# DMTV_SD.net
KiCad netlist of a schematic drawn in EAGLE
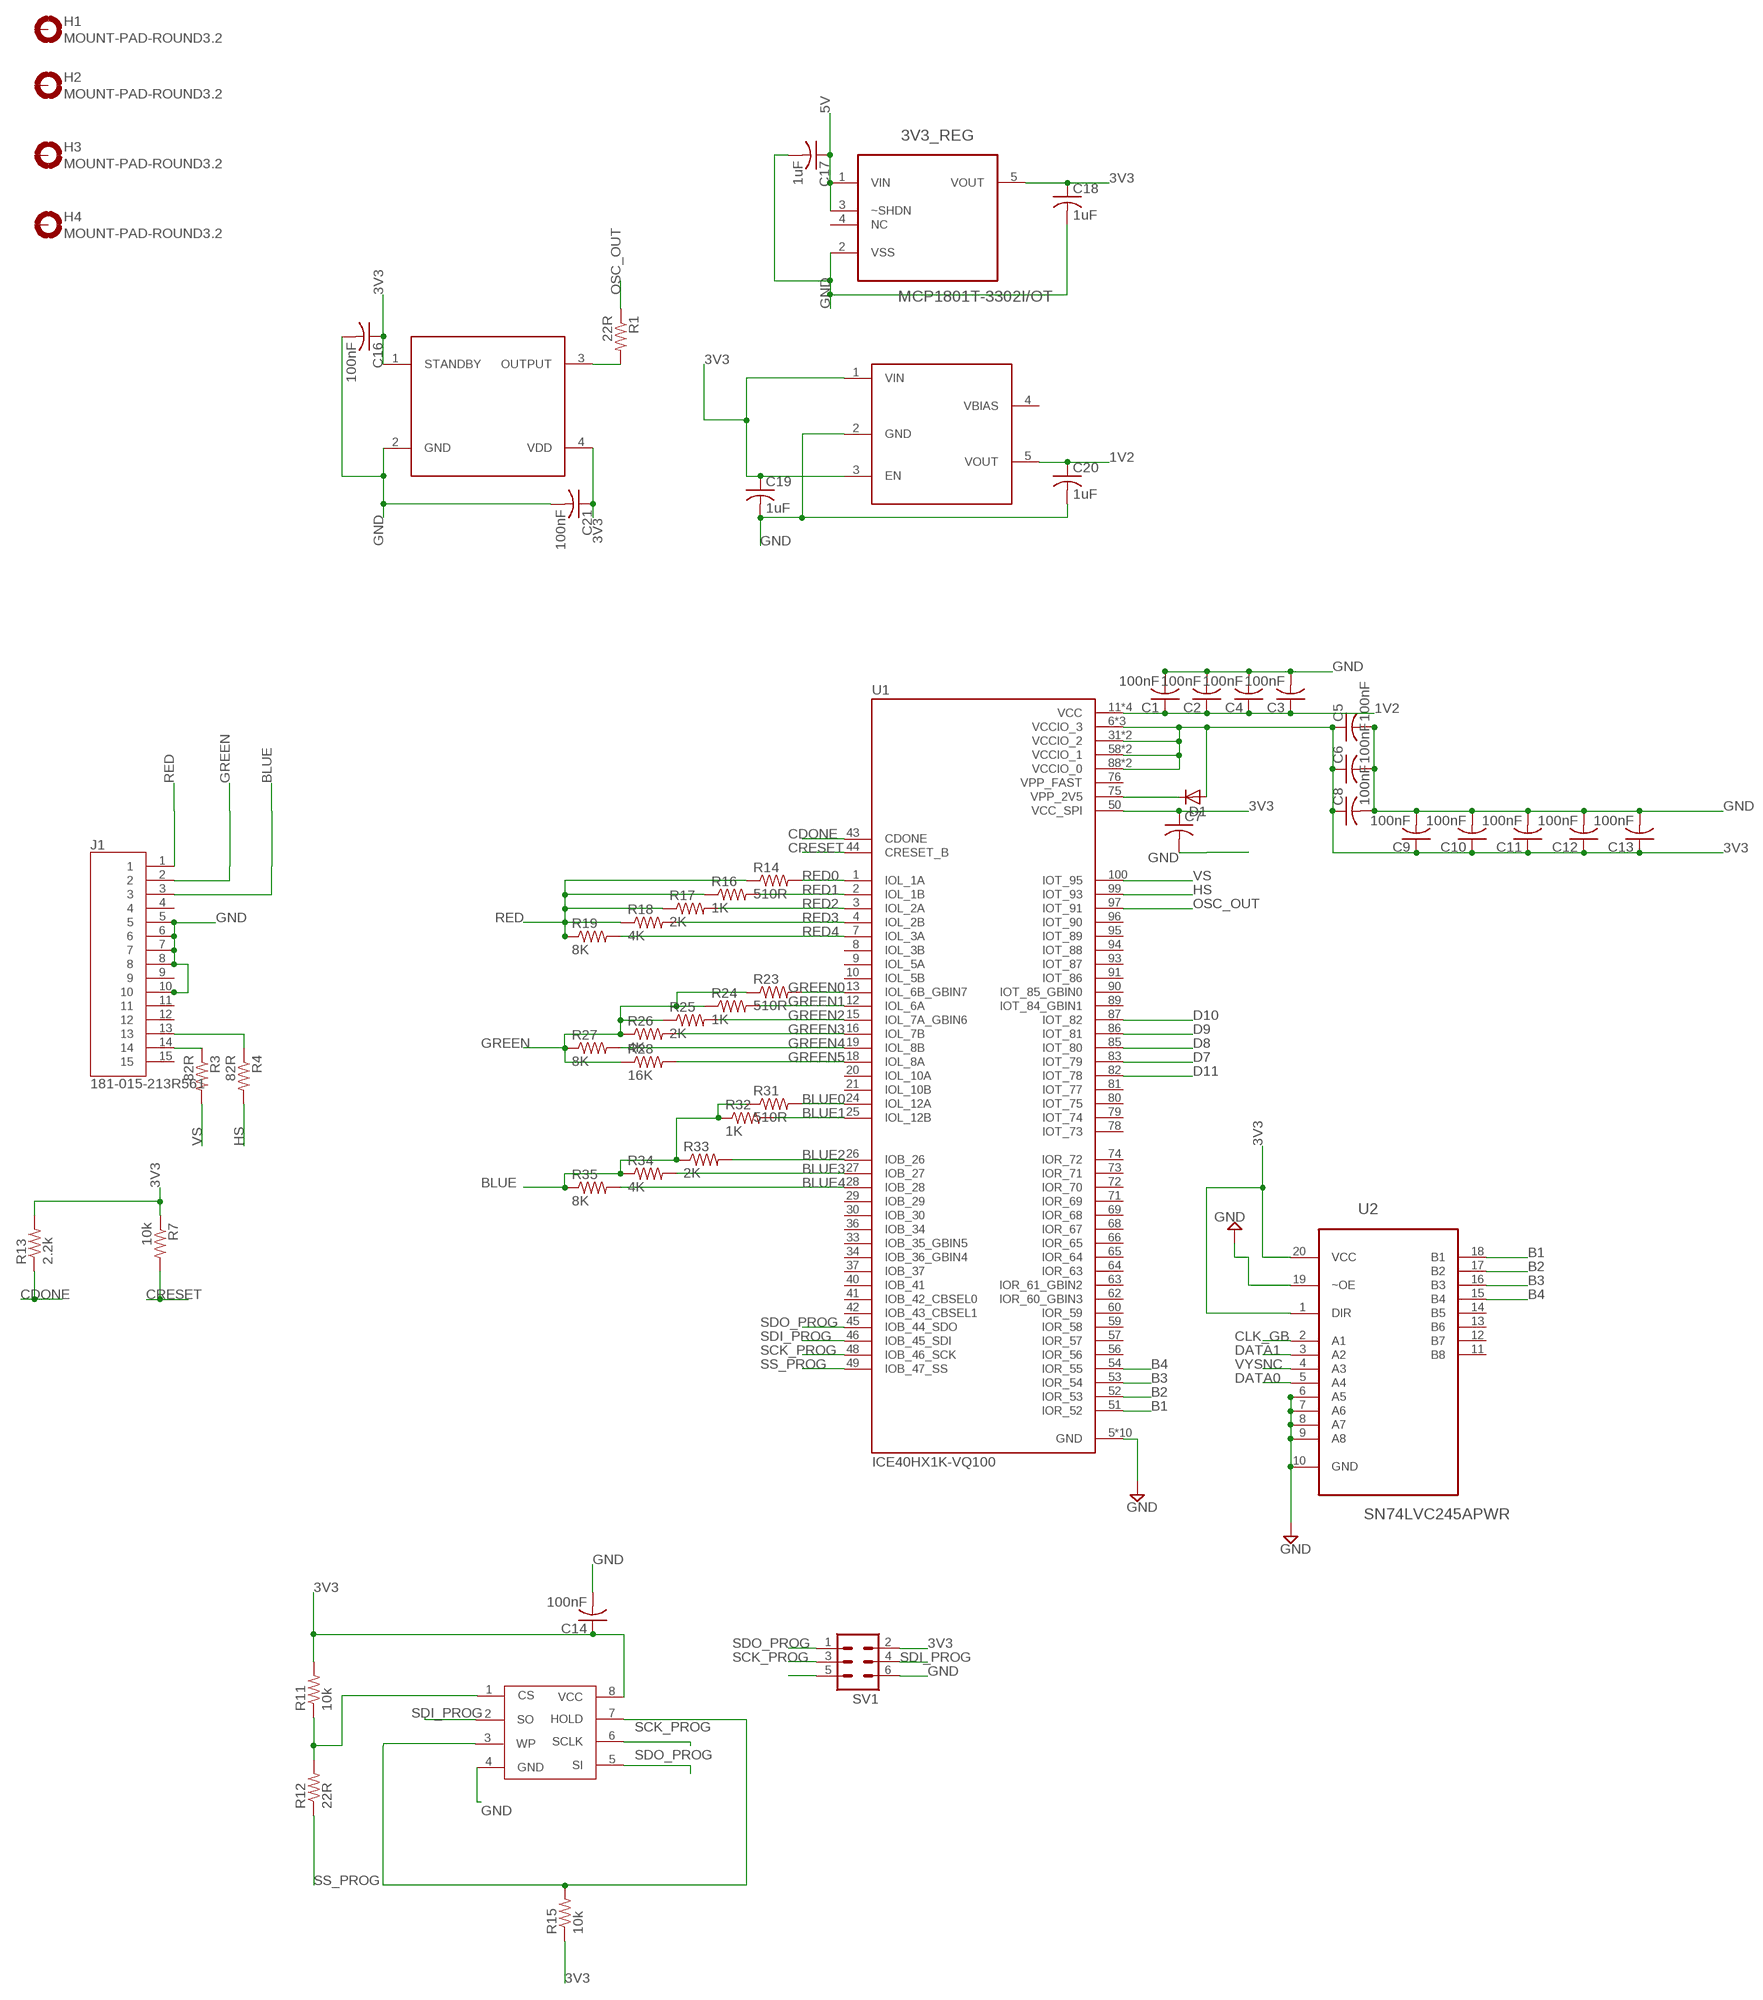
[diagram p0: schematic, sheet 1]
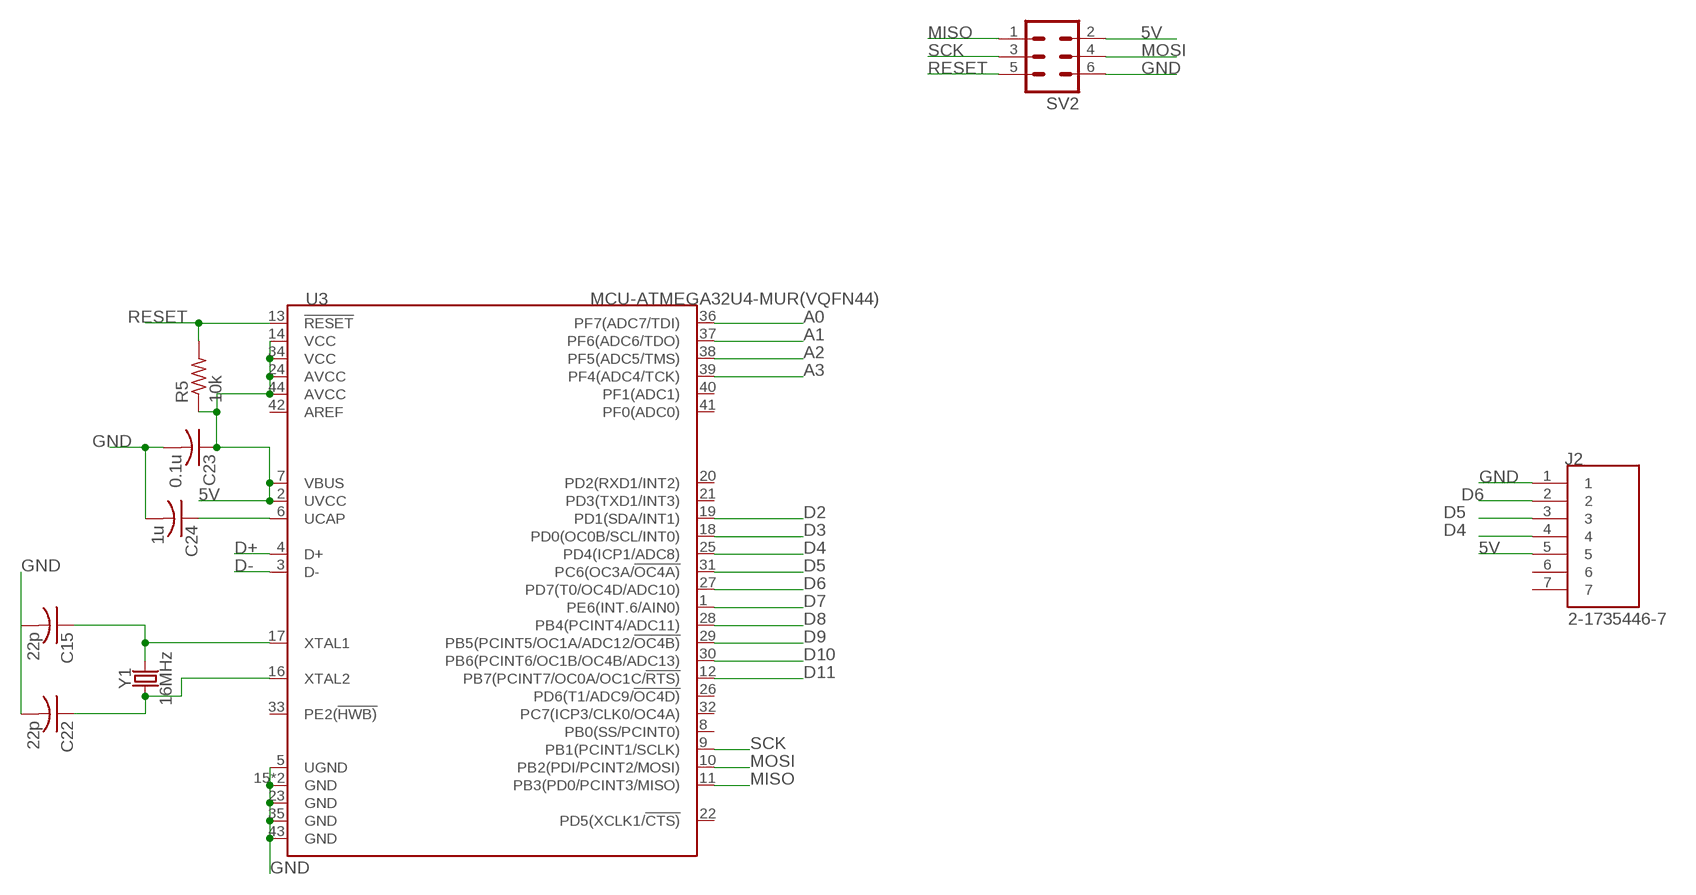
[diagram p1: schematic, sheet 2]
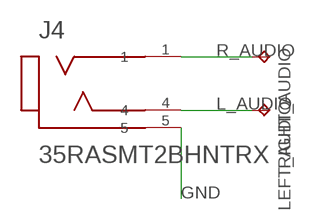
[diagram p2: schematic, sheet 3]
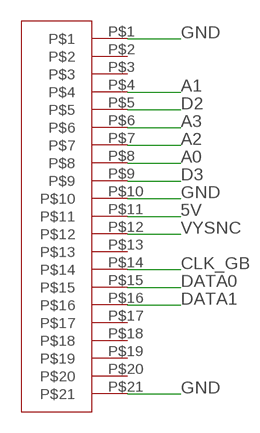
[diagram p3: schematic, sheet 4]

(export (version "E")
  (design (tool "Eeschema 10.0.6"))
  (components
    (comp (ref "C15")
      (value "22p")
      (footprint "eagle-import:C0805")
      (libsource (lib "eagle-import") (part "C-USC0805"))
    )
    (comp (ref "C22")
      (value "22p")
      (footprint "eagle-import:C0805")
      (libsource (lib "eagle-import") (part "C-USC0805"))
    )
    (comp (ref "C23")
      (value "0.1u")
      (footprint "eagle-import:C0805")
      (libsource (lib "eagle-import") (part "C-USC0805"))
    )
    (comp (ref "C24")
      (value "1u")
      (footprint "eagle-import:C0805")
      (libsource (lib "eagle-import") (part "C-USC0805"))
    )
    (comp (ref "J2")
      (value "2-1735446-7")
      (footprint "eagle-import:TE_2-1735446-7")
      (fields (field (name "MF") "TE Connectivity"))
      (libsource (lib "eagle-import") (part "2-1735446-7"))
    )
    (comp (ref "R5")
      (value "10k")
      (footprint "eagle-import:R0805")
      (libsource (lib "eagle-import") (part "R-US_R0805"))
    )
    (comp (ref "SV2")
      (value "MA03-2")
      (footprint "eagle-import:MA03-2")
      (libsource (lib "eagle-import") (part "MA03-2"))
    )
    (comp (ref "U3")
      (value "MCU-ATMEGA32U4-MUR(VQFN44)")
      (footprint "eagle-import:QFN44G-0.5-7X7MM")
      (fields (field (name "MF") "Microchip") (field (name "MP") "ATMEGA32U4-MUR"))
      (libsource (lib "eagle-import") (part "MCU-ATMEGA32U4-MUR(VQFN44)"))
    )
    (comp (ref "Y1")
      (value "16MHz")
      (footprint "eagle-import:CRYSTAL-SMD-5X3.2-4PAD")
      (libsource (lib "eagle-import") (part "CRYSTAL-16MHZSMD-5X3.2"))
    )
    (comp (ref "U$6")
      (value "52808-21700520452145")
      (footprint "eagle-import:0520452145")
      (libsource (lib "eagle-import") (part "52808-21700520452145"))
    )
    (comp (ref "3V3_REG")
      (value "MCP1801T-3302I/OT")
      (footprint "eagle-import:SOT95P270X145-5N")
      (fields (field (name "DIGI-KEY_PART_NUMBER") "MCP1801T-3302I/OTCT-ND") (field (name "MF") "Microchip"))
      (libsource (lib "eagle-import") (part "MCP1801T-3302I/OT"))
    )
    (comp (ref "C1")
      (value "100nF")
      (footprint "eagle-import:C0603")
      (libsource (lib "eagle-import") (part "C-USC0603"))
    )
    (comp (ref "C2")
      (value "100nF")
      (footprint "eagle-import:C0603")
      (libsource (lib "eagle-import") (part "C-USC0603"))
    )
    (comp (ref "C3")
      (value "100nF")
      (footprint "eagle-import:C0603")
      (libsource (lib "eagle-import") (part "C-USC0603"))
    )
    (comp (ref "C4")
      (value "100nF")
      (footprint "eagle-import:C0603")
      (libsource (lib "eagle-import") (part "C-USC0603"))
    )
    (comp (ref "C5")
      (value "100nF")
      (footprint "eagle-import:C0603")
      (libsource (lib "eagle-import") (part "C-USC0603"))
    )
    (comp (ref "C6")
      (value "100nF")
      (footprint "eagle-import:C0603")
      (libsource (lib "eagle-import") (part "C-USC0603"))
    )
    (comp (ref "C7")
      (value "C-USC0603")
      (footprint "eagle-import:C0603")
      (libsource (lib "eagle-import") (part "C-USC0603"))
    )
    (comp (ref "C8")
      (value "100nF")
      (footprint "eagle-import:C0603")
      (libsource (lib "eagle-import") (part "C-USC0603"))
    )
    (comp (ref "C9")
      (value "100nF")
      (footprint "eagle-import:C0603")
      (libsource (lib "eagle-import") (part "C-USC0603"))
    )
    (comp (ref "C10")
      (value "100nF")
      (footprint "eagle-import:C0603")
      (libsource (lib "eagle-import") (part "C-USC0603"))
    )
    (comp (ref "C11")
      (value "100nF")
      (footprint "eagle-import:C0603")
      (libsource (lib "eagle-import") (part "C-USC0603"))
    )
    (comp (ref "C12")
      (value "100nF")
      (footprint "eagle-import:C0603")
      (libsource (lib "eagle-import") (part "C-USC0603"))
    )
    (comp (ref "C13")
      (value "100nF")
      (footprint "eagle-import:C0603")
      (libsource (lib "eagle-import") (part "C-USC0603"))
    )
    (comp (ref "C14")
      (value "100nF")
      (footprint "eagle-import:C0603")
      (libsource (lib "eagle-import") (part "C-USC0603"))
    )
    (comp (ref "C16")
      (value "100nF")
      (footprint "eagle-import:C0603")
      (libsource (lib "eagle-import") (part "C-USC0603"))
    )
    (comp (ref "C17")
      (value "1uF")
      (footprint "eagle-import:C0805")
      (libsource (lib "eagle-import") (part "C-USC0805"))
    )
    (comp (ref "C18")
      (value "1uF")
      (footprint "eagle-import:C0805")
      (libsource (lib "eagle-import") (part "C-USC0805"))
    )
    (comp (ref "C19")
      (value "1uF")
      (footprint "eagle-import:C0805")
      (libsource (lib "eagle-import") (part "C-USC0805"))
    )
    (comp (ref "C20")
      (value "1uF")
      (footprint "eagle-import:C0805")
      (libsource (lib "eagle-import") (part "C-USC0805"))
    )
    (comp (ref "C21")
      (value "100nF")
      (footprint "eagle-import:C0603")
      (libsource (lib "eagle-import") (part "C-USC0603"))
    )
    (comp (ref "D1")
      (value "D-SOD123")
      (footprint "eagle-import:SOD123")
      (libsource (lib "eagle-import") (part "D-SOD123"))
    )
    (comp (ref "H1")
      (value "MOUNT-PAD-ROUND3.2")
      (footprint "eagle-import:3,2-PAD")
      (libsource (lib "eagle-import") (part "MOUNT-PAD-ROUND3.2"))
    )
    (comp (ref "H2")
      (value "MOUNT-PAD-ROUND3.2")
      (footprint "eagle-import:3,2-PAD")
      (libsource (lib "eagle-import") (part "MOUNT-PAD-ROUND3.2"))
    )
    (comp (ref "H3")
      (value "MOUNT-PAD-ROUND3.2")
      (footprint "eagle-import:3,2-PAD")
      (libsource (lib "eagle-import") (part "MOUNT-PAD-ROUND3.2"))
    )
    (comp (ref "H4")
      (value "MOUNT-PAD-ROUND3.2")
      (footprint "eagle-import:3,2-PAD")
      (libsource (lib "eagle-import") (part "MOUNT-PAD-ROUND3.2"))
    )
    (comp (ref "J1")
      (value "181-015-213R561")
      (footprint "eagle-import:NORCOMP_181-015-213R561")
      (fields (field (name "MF") "NorComp Inc."))
      (libsource (lib "eagle-import") (part "181-015-213R561"))
    )
    (comp (ref "R1")
      (value "22R")
      (footprint "eagle-import:R0603")
      (libsource (lib "eagle-import") (part "resistor_348_R-US_R0603"))
    )
    (comp (ref "R3")
      (value "82R")
      (footprint "eagle-import:R0603")
      (libsource (lib "eagle-import") (part "resistor_348_R-US_R0603"))
    )
    (comp (ref "R4")
      (value "82R")
      (footprint "eagle-import:R0603")
      (libsource (lib "eagle-import") (part "resistor_348_R-US_R0603"))
    )
    (comp (ref "R7")
      (value "10k")
      (footprint "eagle-import:R0603")
      (libsource (lib "eagle-import") (part "resistor_348_R-US_R0603"))
    )
    (comp (ref "R11")
      (value "10k")
      (footprint "eagle-import:R0603")
      (libsource (lib "eagle-import") (part "R-US_R0603"))
    )
    (comp (ref "R12")
      (value "22R")
      (footprint "eagle-import:R0603")
      (libsource (lib "eagle-import") (part "R-US_R0603"))
    )
    (comp (ref "R13")
      (value "2.2k")
      (footprint "eagle-import:R0603")
      (libsource (lib "eagle-import") (part "R-US_R0603"))
    )
    (comp (ref "R14")
      (value "510R")
      (footprint "eagle-import:R0603")
      (libsource (lib "eagle-import") (part "resistor_348_R-US_R0603"))
    )
    (comp (ref "R15")
      (value "10k")
      (footprint "eagle-import:R0603")
      (libsource (lib "eagle-import") (part "R-US_R0603"))
    )
    (comp (ref "R16")
      (value "1K")
      (footprint "eagle-import:R0603")
      (libsource (lib "eagle-import") (part "resistor_348_R-US_R0603"))
    )
    (comp (ref "R17")
      (value "2K")
      (footprint "eagle-import:R0603")
      (libsource (lib "eagle-import") (part "resistor_348_R-US_R0603"))
    )
    (comp (ref "R18")
      (value "4K")
      (footprint "eagle-import:R0603")
      (libsource (lib "eagle-import") (part "resistor_348_R-US_R0603"))
    )
    (comp (ref "R19")
      (value "8K")
      (footprint "eagle-import:R0603")
      (libsource (lib "eagle-import") (part "resistor_348_R-US_R0603"))
    )
    (comp (ref "R23")
      (value "510R")
      (footprint "eagle-import:R0603")
      (libsource (lib "eagle-import") (part "resistor_348_R-US_R0603"))
    )
    (comp (ref "R24")
      (value "1K")
      (footprint "eagle-import:R0603")
      (libsource (lib "eagle-import") (part "resistor_348_R-US_R0603"))
    )
    (comp (ref "R25")
      (value "2K")
      (footprint "eagle-import:R0603")
      (libsource (lib "eagle-import") (part "resistor_348_R-US_R0603"))
    )
    (comp (ref "R26")
      (value "4K")
      (footprint "eagle-import:R0603")
      (libsource (lib "eagle-import") (part "resistor_348_R-US_R0603"))
    )
    (comp (ref "R27")
      (value "8K")
      (footprint "eagle-import:R0603")
      (libsource (lib "eagle-import") (part "resistor_348_R-US_R0603"))
    )
    (comp (ref "R28")
      (value "16K")
      (footprint "eagle-import:R0603")
      (libsource (lib "eagle-import") (part "resistor_348_R-US_R0603"))
    )
    (comp (ref "R31")
      (value "510R")
      (footprint "eagle-import:R0603")
      (libsource (lib "eagle-import") (part "resistor_348_R-US_R0603"))
    )
    (comp (ref "R32")
      (value "1K")
      (footprint "eagle-import:R0603")
      (libsource (lib "eagle-import") (part "resistor_348_R-US_R0603"))
    )
    (comp (ref "R33")
      (value "2K")
      (footprint "eagle-import:R0603")
      (libsource (lib "eagle-import") (part "resistor_348_R-US_R0603"))
    )
    (comp (ref "R34")
      (value "4K")
      (footprint "eagle-import:R0603")
      (libsource (lib "eagle-import") (part "resistor_348_R-US_R0603"))
    )
    (comp (ref "R35")
      (value "8K")
      (footprint "eagle-import:R0603")
      (libsource (lib "eagle-import") (part "resistor_348_R-US_R0603"))
    )
    (comp (ref "SV1")
      (value "MA03-2")
      (footprint "eagle-import:MA03-2")
      (libsource (lib "eagle-import") (part "MA03-2"))
    )
    (comp (ref "U$1")
      (value "SIT8008BI-13-18E-25.175000G")
      (footprint "eagle-import:XTAL_ASDM1-25.000MHZ-LC-T")
      (libsource (lib "eagle-import") (part "XTAL_ASDM1-25.000MHZ-LC-T"))
    )
    (comp (ref "U$2")
      (value "TLV70012DDCR")
      (footprint "eagle-import:SOT95P280X100-5N")
      (libsource (lib "eagle-import") (part "SOT95P280X100-5N"))
    )
    (comp (ref "U$5")
      (value "MX25L1006EMI-10G")
      (footprint "eagle-import:SOIC-8")
      (libsource (lib "eagle-import") (part "MX25L1006EMI-10G"))
    )
    (comp (ref "U1")
      (value "ICE40HX1K-VQ100")
      (footprint "eagle-import:QFP50P1600X1600X120-100N")
      (fields (field (name "DIGI-KEY_PART_NUMBER") "220-1567-ND") (field (name "MF") "Lattice Semiconductor"))
      (libsource (lib "eagle-import") (part "ICE40HX1K-VQ100"))
    )
    (comp (ref "U2")
      (value "SN74LVC245APWR")
      (footprint "eagle-import:SOP65P640X120-20N")
      (fields (field (name "DIGI-KEY_PART_NUMBER") "296-1233-1-ND") (field (name "MF") "Texas Instruments"))
      (libsource (lib "eagle-import") (part "SN74LVC245APWR"))
    )
    (comp (ref "J4")
      (value "35RASMT2BHNTRX")
      (footprint "eagle-import:SWITCHCRAFT_35RASMT2BHNTRX")
      (fields (field (name "MF") "Switchcraft"))
      (libsource (lib "eagle-import") (part "35RASMT2BHNTRX"))
    )
    (comp (ref "LEFT_AUDIO")
      (value "TPB2,54")
      (footprint "eagle-import:B2,54")
      (libsource (lib "eagle-import") (part "TPB2,54"))
    )
    (comp (ref "RIGHT_AUDIO")
      (value "TPB2,54")
      (footprint "eagle-import:B2,54")
      (libsource (lib "eagle-import") (part "TPB2,54"))
    )
  )
  (nets
    (net (code "1") (name "1V2") (class "Default")
      (node (ref "C1") (pin "1") (pinfunction "1_1") (pintype "passive"))
      (node (ref "C2") (pin "1") (pinfunction "1_1") (pintype "passive"))
      (node (ref "C20") (pin "1") (pinfunction "1_1") (pintype "passive"))
      (node (ref "C3") (pin "1") (pinfunction "1_1") (pintype "passive"))
      (node (ref "C4") (pin "1") (pinfunction "1_1") (pintype "passive"))
      (node (ref "U$2") (pin "5") (pinfunction "VOUT_5") (pintype "bidirectional"))
      (node (ref "U1") (pin "11") (pinfunction "VCC_11") (pintype "power_in"))
      (node (ref "U1") (pin "35") (pinfunction "VCC_35") (pintype "power_in"))
      (node (ref "U1") (pin "61") (pinfunction "VCC_61") (pintype "power_in"))
      (node (ref "U1") (pin "77") (pinfunction "VCC_77") (pintype "power_in"))
    )
    (net (code "2") (name "3V3") (class "Default")
      (node (ref "3V3_REG") (pin "5") (pinfunction "VOUT_5") (pintype "output"))
      (node (ref "C10") (pin "1") (pinfunction "1_1") (pintype "passive"))
      (node (ref "C11") (pin "1") (pinfunction "1_1") (pintype "passive"))
      (node (ref "C12") (pin "1") (pinfunction "1_1") (pintype "passive"))
      (node (ref "C13") (pin "1") (pinfunction "1_1") (pintype "passive"))
      (node (ref "C14") (pin "1") (pinfunction "1_1") (pintype "passive"))
      (node (ref "C16") (pin "1") (pinfunction "1_1") (pintype "passive"))
      (node (ref "C18") (pin "1") (pinfunction "1_1") (pintype "passive"))
      (node (ref "C19") (pin "1") (pinfunction "1_1") (pintype "passive"))
      (node (ref "C21") (pin "1") (pinfunction "1_1") (pintype "passive"))
      (node (ref "C5") (pin "1") (pinfunction "1_1") (pintype "passive"))
      (node (ref "C6") (pin "1") (pinfunction "1_1") (pintype "passive"))
      (node (ref "C7") (pin "1") (pinfunction "1_1") (pintype "passive"))
      (node (ref "C8") (pin "1") (pinfunction "1_1") (pintype "passive"))
      (node (ref "C9") (pin "1") (pinfunction "1_1") (pintype "passive"))
      (node (ref "D1") (pin "2") (pinfunction "A_2") (pintype "passive"))
      (node (ref "R11") (pin "2") (pinfunction "2_2") (pintype "passive"))
      (node (ref "R13") (pin "2") (pinfunction "2_2") (pintype "passive"))
      (node (ref "R15") (pin "1") (pinfunction "1_1") (pintype "passive"))
      (node (ref "R7") (pin "1") (pinfunction "1_1") (pintype "passive"))
      (node (ref "SV1") (pin "2") (pinfunction "2_2") (pintype "passive"))
      (node (ref "U$1") (pin "1") (pinfunction "STANDBY_1") (pintype "bidirectional"))
      (node (ref "U$1") (pin "4") (pinfunction "VDD_4") (pintype "bidirectional"))
      (node (ref "U$2") (pin "1") (pinfunction "VIN_1") (pintype "bidirectional"))
      (node (ref "U$2") (pin "3") (pinfunction "EN_3") (pintype "bidirectional"))
      (node (ref "U$5") (pin "8") (pinfunction "VCC_8") (pintype "bidirectional"))
      (node (ref "U1") (pin "14") (pinfunction "VCCIO_3_14") (pintype "power_in"))
      (node (ref "U1") (pin "22") (pinfunction "VCCIO_3_22") (pintype "power_in"))
      (node (ref "U1") (pin "31") (pinfunction "VCCIO_2_31") (pintype "power_in"))
      (node (ref "U1") (pin "38") (pinfunction "VCCIO_2_38") (pintype "power_in"))
      (node (ref "U1") (pin "50") (pinfunction "VCC_SPI_50") (pintype "power_in"))
      (node (ref "U1") (pin "58") (pinfunction "VCCIO_1_58") (pintype "power_in"))
      (node (ref "U1") (pin "6") (pinfunction "VCCIO_3_6") (pintype "power_in"))
      (node (ref "U1") (pin "67") (pinfunction "VCCIO_1_67") (pintype "power_in"))
      (node (ref "U1") (pin "88") (pinfunction "VCCIO_0_88") (pintype "power_in"))
      (node (ref "U1") (pin "92") (pinfunction "VCCIO_0_92") (pintype "power_in"))
      (node (ref "U2") (pin "1") (pinfunction "DIR_1") (pintype "input"))
      (node (ref "U2") (pin "20") (pinfunction "VCC_20") (pintype "power_in"))
    )
    (net (code "3") (name "5V") (class "Default")
      (node (ref "3V3_REG") (pin "1") (pinfunction "VIN_1") (pintype "power_in"))
      (node (ref "3V3_REG") (pin "3") (pinfunction "~{SHDN}_3") (pintype "input"))
      (node (ref "C17") (pin "1") (pinfunction "1_1") (pintype "passive"))
      (node (ref "C23") (pin "1") (pinfunction "1_1") (pintype "passive"))
      (node (ref "J2") (pin "5") (pinfunction "5_5") (pintype "passive"))
      (node (ref "R5") (pin "1") (pinfunction "1_1") (pintype "passive"))
      (node (ref "SV2") (pin "2") (pinfunction "2_2") (pintype "passive"))
      (node (ref "U$6") (pin "P$11") (pinfunction "P$11_P$11") (pintype "bidirectional"))
      (node (ref "U3") (pin "14") (pinfunction "VCC_14") (pintype "bidirectional"))
      (node (ref "U3") (pin "2") (pinfunction "UVCC_2") (pintype "bidirectional"))
      (node (ref "U3") (pin "24") (pinfunction "AVCC_24") (pintype "bidirectional"))
      (node (ref "U3") (pin "34") (pinfunction "VCC_34") (pintype "bidirectional"))
      (node (ref "U3") (pin "44") (pinfunction "AVCC_44") (pintype "bidirectional"))
      (node (ref "U3") (pin "7") (pinfunction "VBUS_7") (pintype "bidirectional"))
    )
    (net (code "4") (name "A0") (class "Default")
      (node (ref "U$6") (pin "P$8") (pinfunction "P$8_P$8") (pintype "bidirectional"))
      (node (ref "U3") (pin "36") (pinfunction "PF7(ADC7/TDI)_36") (pintype "bidirectional"))
    )
    (net (code "5") (name "A1") (class "Default")
      (node (ref "U$6") (pin "P$4") (pinfunction "P$4_P$4") (pintype "bidirectional"))
      (node (ref "U3") (pin "37") (pinfunction "PF6(ADC6/TDO)_37") (pintype "bidirectional"))
    )
    (net (code "6") (name "A2") (class "Default")
      (node (ref "U$6") (pin "P$7") (pinfunction "P$7_P$7") (pintype "bidirectional"))
      (node (ref "U3") (pin "38") (pinfunction "PF5(ADC5/TMS)_38") (pintype "bidirectional"))
    )
    (net (code "7") (name "A3") (class "Default")
      (node (ref "U$6") (pin "P$6") (pinfunction "P$6_P$6") (pintype "bidirectional"))
      (node (ref "U3") (pin "39") (pinfunction "PF4(ADC4/TCK)_39") (pintype "bidirectional"))
    )
    (net (code "8") (name "B1") (class "Default")
      (node (ref "U1") (pin "51") (pinfunction "IOR_52_51") (pintype "bidirectional"))
      (node (ref "U2") (pin "18") (pinfunction "B1_18") (pintype "bidirectional"))
    )
    (net (code "9") (name "B2") (class "Default")
      (node (ref "U1") (pin "52") (pinfunction "IOR_53_52") (pintype "bidirectional"))
      (node (ref "U2") (pin "17") (pinfunction "B2_17") (pintype "bidirectional"))
    )
    (net (code "10") (name "B3") (class "Default")
      (node (ref "U1") (pin "53") (pinfunction "IOR_54_53") (pintype "bidirectional"))
      (node (ref "U2") (pin "16") (pinfunction "B3_16") (pintype "bidirectional"))
    )
    (net (code "11") (name "B4") (class "Default")
      (node (ref "U1") (pin "54") (pinfunction "IOR_55_54") (pintype "bidirectional"))
      (node (ref "U2") (pin "15") (pinfunction "B4_15") (pintype "bidirectional"))
    )
    (net (code "12") (name "BLUE") (class "Default")
      (node (ref "J1") (pin "3") (pinfunction "3_3") (pintype "passive"))
      (node (ref "R31") (pin "1") (pinfunction "1_1") (pintype "passive"))
      (node (ref "R32") (pin "1") (pinfunction "1_1") (pintype "passive"))
      (node (ref "R33") (pin "1") (pinfunction "1_1") (pintype "passive"))
      (node (ref "R34") (pin "1") (pinfunction "1_1") (pintype "passive"))
      (node (ref "R35") (pin "1") (pinfunction "1_1") (pintype "passive"))
    )
    (net (code "13") (name "BLUE0") (class "Default")
      (node (ref "R31") (pin "2") (pinfunction "2_2") (pintype "passive"))
      (node (ref "U1") (pin "24") (pinfunction "IOL_12A_24") (pintype "bidirectional"))
    )
    (net (code "14") (name "BLUE1") (class "Default")
      (node (ref "R32") (pin "2") (pinfunction "2_2") (pintype "passive"))
      (node (ref "U1") (pin "25") (pinfunction "IOL_12B_25") (pintype "bidirectional"))
    )
    (net (code "15") (name "BLUE2") (class "Default")
      (node (ref "R33") (pin "2") (pinfunction "2_2") (pintype "passive"))
      (node (ref "U1") (pin "26") (pinfunction "IOB_26_26") (pintype "bidirectional"))
    )
    (net (code "16") (name "BLUE3") (class "Default")
      (node (ref "R34") (pin "2") (pinfunction "2_2") (pintype "passive"))
      (node (ref "U1") (pin "27") (pinfunction "IOB_27_27") (pintype "bidirectional"))
    )
    (net (code "17") (name "BLUE4") (class "Default")
      (node (ref "R35") (pin "2") (pinfunction "2_2") (pintype "passive"))
      (node (ref "U1") (pin "28") (pinfunction "IOB_28_28") (pintype "bidirectional"))
    )
    (net (code "18") (name "CDONE") (class "Default")
      (node (ref "R13") (pin "1") (pinfunction "1_1") (pintype "passive"))
      (node (ref "U1") (pin "43") (pinfunction "CDONE_43") (pintype "input"))
    )
    (net (code "19") (name "CLK_GB") (class "Default")
      (node (ref "U$6") (pin "P$14") (pinfunction "P$14_P$14") (pintype "bidirectional"))
      (node (ref "U2") (pin "2") (pinfunction "A1_2") (pintype "bidirectional"))
    )
    (net (code "20") (name "CRESET") (class "Default")
      (node (ref "R7") (pin "2") (pinfunction "2_2") (pintype "passive"))
      (node (ref "U1") (pin "44") (pinfunction "CRESET_B_44") (pintype "input"))
    )
    (net (code "21") (name "D+") (class "Default")
      (node (ref "U3") (pin "4") (pinfunction "D+_4") (pintype "bidirectional"))
    )
    (net (code "22") (name "D-") (class "Default")
      (node (ref "U3") (pin "3") (pinfunction "D-_3") (pintype "bidirectional"))
    )
    (net (code "23") (name "D2") (class "Default")
      (node (ref "U$6") (pin "P$5") (pinfunction "P$5_P$5") (pintype "bidirectional"))
      (node (ref "U3") (pin "19") (pinfunction "PD1(SDA/INT1)_19") (pintype "bidirectional"))
    )
    (net (code "24") (name "D3") (class "Default")
      (node (ref "U$6") (pin "P$9") (pinfunction "P$9_P$9") (pintype "bidirectional"))
      (node (ref "U3") (pin "18") (pinfunction "PD0(OC0B/SCL/INT0)_18") (pintype "bidirectional"))
    )
    (net (code "25") (name "D4") (class "Default")
      (node (ref "J2") (pin "4") (pinfunction "4_4") (pintype "passive"))
      (node (ref "U3") (pin "25") (pinfunction "PD4(ICP1/ADC8)_25") (pintype "bidirectional"))
    )
    (net (code "26") (name "D5") (class "Default")
      (node (ref "J2") (pin "3") (pinfunction "3_3") (pintype "passive"))
      (node (ref "U3") (pin "31") (pinfunction "PC6(OC3A/~{OC4A})_31") (pintype "bidirectional"))
    )
    (net (code "27") (name "D6") (class "Default")
      (node (ref "J2") (pin "2") (pinfunction "2_2") (pintype "passive"))
      (node (ref "U3") (pin "27") (pinfunction "PD7(T0/OC4D/ADC10)_27") (pintype "bidirectional"))
    )
    (net (code "28") (name "D7") (class "Default")
      (node (ref "U1") (pin "83") (pinfunction "IOT_79_83") (pintype "bidirectional"))
      (node (ref "U3") (pin "1") (pinfunction "PE6(INT.6/AIN0)_1") (pintype "bidirectional"))
    )
    (net (code "29") (name "D8") (class "Default")
      (node (ref "U1") (pin "85") (pinfunction "IOT_80_85") (pintype "bidirectional"))
      (node (ref "U3") (pin "28") (pinfunction "PB4(PCINT4/ADC11)_28") (pintype "bidirectional"))
    )
    (net (code "30") (name "D9") (class "Default")
      (node (ref "U1") (pin "86") (pinfunction "IOT_81_86") (pintype "bidirectional"))
      (node (ref "U3") (pin "29") (pinfunction "PB5(PCINT5/OC1A/ADC12/~{OC4B})_29") (pintype "bidirectional"))
    )
    (net (code "31") (name "D10") (class "Default")
      (node (ref "U1") (pin "87") (pinfunction "IOT_82_87") (pintype "bidirectional"))
      (node (ref "U3") (pin "30") (pinfunction "PB6(PCINT6/OC1B/OC4B/ADC13)_30") (pintype "bidirectional"))
    )
    (net (code "32") (name "D11") (class "Default")
      (node (ref "U1") (pin "82") (pinfunction "IOT_78_82") (pintype "bidirectional"))
      (node (ref "U3") (pin "12") (pinfunction "PB7(PCINT7/OC0A/OC1C/~{RTS})_12") (pintype "bidirectional"))
    )
    (net (code "33") (name "DATA0") (class "Default")
      (node (ref "U$6") (pin "P$15") (pinfunction "P$15_P$15") (pintype "bidirectional"))
      (node (ref "U2") (pin "5") (pinfunction "A4_5") (pintype "bidirectional"))
    )
    (net (code "34") (name "DATA1") (class "Default")
      (node (ref "U$6") (pin "P$16") (pinfunction "P$16_P$16") (pintype "bidirectional"))
      (node (ref "U2") (pin "3") (pinfunction "A2_3") (pintype "bidirectional"))
    )
    (net (code "35") (name "GND") (class "Default")
      (node (ref "3V3_REG") (pin "2") (pinfunction "VSS_2") (pintype "passive"))
      (node (ref "C1") (pin "2") (pinfunction "2_2") (pintype "passive"))
      (node (ref "C10") (pin "2") (pinfunction "2_2") (pintype "passive"))
      (node (ref "C11") (pin "2") (pinfunction "2_2") (pintype "passive"))
      (node (ref "C12") (pin "2") (pinfunction "2_2") (pintype "passive"))
      (node (ref "C13") (pin "2") (pinfunction "2_2") (pintype "passive"))
      (node (ref "C14") (pin "2") (pinfunction "2_2") (pintype "passive"))
      (node (ref "C15") (pin "2") (pinfunction "2_2") (pintype "passive"))
      (node (ref "C16") (pin "2") (pinfunction "2_2") (pintype "passive"))
      (node (ref "C17") (pin "2") (pinfunction "2_2") (pintype "passive"))
      (node (ref "C18") (pin "2") (pinfunction "2_2") (pintype "passive"))
      (node (ref "C19") (pin "2") (pinfunction "2_2") (pintype "passive"))
      (node (ref "C2") (pin "2") (pinfunction "2_2") (pintype "passive"))
      (node (ref "C20") (pin "2") (pinfunction "2_2") (pintype "passive"))
      (node (ref "C21") (pin "2") (pinfunction "2_2") (pintype "passive"))
      (node (ref "C22") (pin "2") (pinfunction "2_2") (pintype "passive"))
      (node (ref "C23") (pin "2") (pinfunction "2_2") (pintype "passive"))
      (node (ref "C24") (pin "2") (pinfunction "2_2") (pintype "passive"))
      (node (ref "C3") (pin "2") (pinfunction "2_2") (pintype "passive"))
      (node (ref "C4") (pin "2") (pinfunction "2_2") (pintype "passive"))
      (node (ref "C5") (pin "2") (pinfunction "2_2") (pintype "passive"))
      (node (ref "C6") (pin "2") (pinfunction "2_2") (pintype "passive"))
      (node (ref "C7") (pin "2") (pinfunction "2_2") (pintype "passive"))
      (node (ref "C8") (pin "2") (pinfunction "2_2") (pintype "passive"))
      (node (ref "C9") (pin "2") (pinfunction "2_2") (pintype "passive"))
      (node (ref "J1") (pin "10") (pinfunction "10_10") (pintype "passive"))
      (node (ref "J1") (pin "5") (pinfunction "5_5") (pintype "passive"))
      (node (ref "J1") (pin "6") (pinfunction "6_6") (pintype "passive"))
      (node (ref "J1") (pin "7") (pinfunction "7_7") (pintype "passive"))
      (node (ref "J1") (pin "8") (pinfunction "8_8") (pintype "passive"))
      (node (ref "J2") (pin "1") (pinfunction "1_1") (pintype "passive"))
      (node (ref "J4") (pin "5") (pinfunction "5_5") (pintype "passive"))
      (node (ref "SV1") (pin "6") (pinfunction "6_6") (pintype "passive"))
      (node (ref "SV2") (pin "6") (pinfunction "6_6") (pintype "passive"))
      (node (ref "U$1") (pin "2") (pinfunction "GND_2") (pintype "bidirectional"))
      (node (ref "U$2") (pin "2") (pinfunction "GND_2") (pintype "bidirectional"))
      (node (ref "U$5") (pin "4") (pinfunction "GND_4") (pintype "bidirectional"))
      (node (ref "U$6") (pin "P$1") (pinfunction "P$1_P$1") (pintype "bidirectional"))
      (node (ref "U$6") (pin "P$10") (pinfunction "P$10_P$10") (pintype "bidirectional"))
      (node (ref "U$6") (pin "P$21") (pinfunction "P$21_P$21") (pintype "bidirectional"))
      (node (ref "U1") (pin "17") (pinfunction "GND_17") (pintype "power_in"))
      (node (ref "U1") (pin "23") (pinfunction "GND_23") (pintype "power_in"))
      (node (ref "U1") (pin "32") (pinfunction "GND_32") (pintype "power_in"))
      (node (ref "U1") (pin "39") (pinfunction "GND_39") (pintype "power_in"))
      (node (ref "U1") (pin "47") (pinfunction "GND_47") (pintype "power_in"))
      (node (ref "U1") (pin "5") (pinfunction "GND_5") (pintype "power_in"))
      (node (ref "U1") (pin "55") (pinfunction "GND_55") (pintype "power_in"))
      (node (ref "U1") (pin "70") (pinfunction "GND_70") (pintype "power_in"))
      (node (ref "U1") (pin "84") (pinfunction "GND_84") (pintype "power_in"))
      (node (ref "U1") (pin "98") (pinfunction "GND_98") (pintype "power_in"))
      (node (ref "U2") (pin "10") (pinfunction "GND_10") (pintype "passive"))
      (node (ref "U2") (pin "19") (pinfunction "~{OE}_19") (pintype "input"))
      (node (ref "U2") (pin "6") (pinfunction "A5_6") (pintype "bidirectional"))
      (node (ref "U2") (pin "7") (pinfunction "A6_7") (pintype "bidirectional"))
      (node (ref "U2") (pin "8") (pinfunction "A7_8") (pintype "bidirectional"))
      (node (ref "U2") (pin "9") (pinfunction "A8_9") (pintype "bidirectional"))
      (node (ref "U3") (pin "15") (pinfunction "GND_15") (pintype "bidirectional"))
      (node (ref "U3") (pin "23") (pinfunction "GND_23") (pintype "bidirectional"))
      (node (ref "U3") (pin "35") (pinfunction "GND_35") (pintype "bidirectional"))
      (node (ref "U3") (pin "43") (pinfunction "GND_43") (pintype "bidirectional"))
      (node (ref "U3") (pin "5") (pinfunction "UGND_5") (pintype "bidirectional"))
      (node (ref "U3") (pin "TAB") (pinfunction "GND_TAB") (pintype "bidirectional"))
    )
    (net (code "36") (name "GREEN") (class "Default")
      (node (ref "J1") (pin "2") (pinfunction "2_2") (pintype "passive"))
      (node (ref "R23") (pin "1") (pinfunction "1_1") (pintype "passive"))
      (node (ref "R24") (pin "1") (pinfunction "1_1") (pintype "passive"))
      (node (ref "R25") (pin "1") (pinfunction "1_1") (pintype "passive"))
      (node (ref "R26") (pin "1") (pinfunction "1_1") (pintype "passive"))
      (node (ref "R27") (pin "1") (pinfunction "1_1") (pintype "passive"))
      (node (ref "R28") (pin "1") (pinfunction "1_1") (pintype "passive"))
    )
    (net (code "37") (name "GREEN0") (class "Default")
      (node (ref "R23") (pin "2") (pinfunction "2_2") (pintype "passive"))
      (node (ref "U1") (pin "13") (pinfunction "IOL_6B_GBIN7_13") (pintype "bidirectional"))
    )
    (net (code "38") (name "GREEN1") (class "Default")
      (node (ref "R24") (pin "2") (pinfunction "2_2") (pintype "passive"))
      (node (ref "U1") (pin "12") (pinfunction "IOL_6A_12") (pintype "bidirectional"))
    )
    (net (code "39") (name "GREEN2") (class "Default")
      (node (ref "R25") (pin "2") (pinfunction "2_2") (pintype "passive"))
      (node (ref "U1") (pin "15") (pinfunction "IOL_7A_GBIN6_15") (pintype "bidirectional"))
    )
    (net (code "40") (name "GREEN3") (class "Default")
      (node (ref "R26") (pin "2") (pinfunction "2_2") (pintype "passive"))
      (node (ref "U1") (pin "16") (pinfunction "IOL_7B_16") (pintype "bidirectional"))
    )
    (net (code "41") (name "GREEN4") (class "Default")
      (node (ref "R27") (pin "2") (pinfunction "2_2") (pintype "passive"))
      (node (ref "U1") (pin "19") (pinfunction "IOL_8B_19") (pintype "bidirectional"))
    )
    (net (code "42") (name "GREEN5") (class "Default")
      (node (ref "R28") (pin "2") (pinfunction "2_2") (pintype "passive"))
      (node (ref "U1") (pin "18") (pinfunction "IOL_8A_18") (pintype "bidirectional"))
    )
    (net (code "43") (name "HS") (class "Default")
      (node (ref "R4") (pin "2") (pinfunction "2_2") (pintype "passive"))
      (node (ref "U1") (pin "99") (pinfunction "IOT_93_99") (pintype "bidirectional"))
    )
    (net (code "44") (name "L_AUDIO") (class "Default")
      (node (ref "J4") (pin "4") (pinfunction "4_4") (pintype "passive"))
      (node (ref "LEFT_AUDIO") (pin "TP") (pinfunction "TP_TP") (pintype "input"))
    )
    (net (code "45") (name "MISO") (class "Default")
      (node (ref "SV2") (pin "1") (pinfunction "1_1") (pintype "passive"))
      (node (ref "U3") (pin "11") (pinfunction "PB3(PD0/PCINT3/MISO)_11") (pintype "bidirectional"))
    )
    (net (code "46") (name "MOSI") (class "Default")
      (node (ref "SV2") (pin "4") (pinfunction "4_4") (pintype "passive"))
      (node (ref "U3") (pin "10") (pinfunction "PB2(PDI/PCINT2/MOSI)_10") (pintype "bidirectional"))
    )
    (net (code "47") (name "Net-(D1-C)") (class "Default")
      (node (ref "D1") (pin "1") (pinfunction "C_1") (pintype "passive"))
      (node (ref "U1") (pin "75") (pinfunction "VPP_2V5_75") (pintype "power_in"))
    )
    (net (code "48") (name "Net-(J1-Pad13)") (class "Default")
      (node (ref "J1") (pin "13") (pinfunction "13_13") (pintype "passive"))
      (node (ref "R4") (pin "1") (pinfunction "1_1") (pintype "passive"))
    )
    (net (code "49") (name "Net-(J1-Pad14)") (class "Default")
      (node (ref "J1") (pin "14") (pinfunction "14_14") (pintype "passive"))
      (node (ref "R3") (pin "1") (pinfunction "1_1") (pintype "passive"))
    )
    (net (code "50") (name "Net-(U$1-OUTPUT)") (class "Default")
      (node (ref "R1") (pin "2") (pinfunction "2_2") (pintype "passive"))
      (node (ref "U$1") (pin "3") (pinfunction "OUTPUT_3") (pintype "bidirectional"))
    )
    (net (code "51") (name "Net-(U$5-CS)") (class "Default")
      (node (ref "R11") (pin "1") (pinfunction "1_1") (pintype "passive"))
      (node (ref "R12") (pin "2") (pinfunction "2_2") (pintype "passive"))
      (node (ref "U$5") (pin "1") (pinfunction "CS_1") (pintype "bidirectional"))
    )
    (net (code "52") (name "Net-(U$5-HOLD)") (class "Default")
      (node (ref "R15") (pin "2") (pinfunction "2_2") (pintype "passive"))
      (node (ref "U$5") (pin "3") (pinfunction "WP_3") (pintype "bidirectional"))
      (node (ref "U$5") (pin "7") (pinfunction "HOLD_7") (pintype "bidirectional"))
    )
    (net (code "53") (name "Net-(U3-UCAP)") (class "Default")
      (node (ref "C24") (pin "1") (pinfunction "1_1") (pintype "passive"))
      (node (ref "U3") (pin "6") (pinfunction "UCAP_6") (pintype "bidirectional"))
    )
    (net (code "54") (name "Net-(U3-XTAL1)") (class "Default")
      (node (ref "C15") (pin "1") (pinfunction "1_1") (pintype "passive"))
      (node (ref "U3") (pin "17") (pinfunction "XTAL1_17") (pintype "bidirectional"))
      (node (ref "Y1") (pin "3") (pinfunction "2_3") (pintype "passive"))
    )
    (net (code "55") (name "Net-(U3-XTAL2)") (class "Default")
      (node (ref "C22") (pin "1") (pinfunction "1_1") (pintype "passive"))
      (node (ref "U3") (pin "16") (pinfunction "XTAL2_16") (pintype "bidirectional"))
      (node (ref "Y1") (pin "1") (pinfunction "1_1") (pintype "passive"))
    )
    (net (code "56") (name "OSC_OUT") (class "Default")
      (node (ref "R1") (pin "1") (pinfunction "1_1") (pintype "passive"))
      (node (ref "U1") (pin "97") (pinfunction "IOT_91_97") (pintype "bidirectional"))
    )
    (net (code "57") (name "RED") (class "Default")
      (node (ref "J1") (pin "1") (pinfunction "1_1") (pintype "passive"))
      (node (ref "R14") (pin "1") (pinfunction "1_1") (pintype "passive"))
      (node (ref "R16") (pin "1") (pinfunction "1_1") (pintype "passive"))
      (node (ref "R17") (pin "1") (pinfunction "1_1") (pintype "passive"))
      (node (ref "R18") (pin "1") (pinfunction "1_1") (pintype "passive"))
      (node (ref "R19") (pin "1") (pinfunction "1_1") (pintype "passive"))
    )
    (net (code "58") (name "RED0") (class "Default")
      (node (ref "R14") (pin "2") (pinfunction "2_2") (pintype "passive"))
      (node (ref "U1") (pin "1") (pinfunction "IOL_1A_1") (pintype "bidirectional"))
    )
    (net (code "59") (name "RED1") (class "Default")
      (node (ref "R16") (pin "2") (pinfunction "2_2") (pintype "passive"))
      (node (ref "U1") (pin "2") (pinfunction "IOL_1B_2") (pintype "bidirectional"))
    )
    (net (code "60") (name "RED2") (class "Default")
      (node (ref "R17") (pin "2") (pinfunction "2_2") (pintype "passive"))
      (node (ref "U1") (pin "3") (pinfunction "IOL_2A_3") (pintype "bidirectional"))
    )
    (net (code "61") (name "RED3") (class "Default")
      (node (ref "R18") (pin "2") (pinfunction "2_2") (pintype "passive"))
      (node (ref "U1") (pin "4") (pinfunction "IOL_2B_4") (pintype "bidirectional"))
    )
    (net (code "62") (name "RED4") (class "Default")
      (node (ref "R19") (pin "2") (pinfunction "2_2") (pintype "passive"))
      (node (ref "U1") (pin "7") (pinfunction "IOL_3A_7") (pintype "bidirectional"))
    )
    (net (code "63") (name "RESET") (class "Default")
      (node (ref "R5") (pin "2") (pinfunction "2_2") (pintype "passive"))
      (node (ref "SV2") (pin "5") (pinfunction "5_5") (pintype "passive"))
      (node (ref "U3") (pin "13") (pinfunction "~{RESET}_13") (pintype "bidirectional"))
    )
    (net (code "64") (name "R_AUDIO") (class "Default")
      (node (ref "J4") (pin "1") (pinfunction "1_1") (pintype "passive"))
      (node (ref "RIGHT_AUDIO") (pin "TP") (pinfunction "TP_TP") (pintype "input"))
    )
    (net (code "65") (name "SCK") (class "Default")
      (node (ref "SV2") (pin "3") (pinfunction "3_3") (pintype "passive"))
      (node (ref "U3") (pin "9") (pinfunction "PB1(PCINT1/SCLK)_9") (pintype "bidirectional"))
    )
    (net (code "66") (name "SCK_PROG") (class "Default")
      (node (ref "SV1") (pin "3") (pinfunction "3_3") (pintype "passive"))
      (node (ref "U$5") (pin "6") (pinfunction "SCLK_6") (pintype "bidirectional"))
      (node (ref "U1") (pin "48") (pinfunction "IOB_46_SCK_48") (pintype "bidirectional"))
    )
    (net (code "67") (name "SDI_PROG") (class "Default")
      (node (ref "SV1") (pin "4") (pinfunction "4_4") (pintype "passive"))
      (node (ref "U$5") (pin "2") (pinfunction "SO_2") (pintype "bidirectional"))
      (node (ref "U1") (pin "46") (pinfunction "IOB_45_SDI_46") (pintype "bidirectional"))
    )
    (net (code "68") (name "SDO_PROG") (class "Default")
      (node (ref "SV1") (pin "1") (pinfunction "1_1") (pintype "passive"))
      (node (ref "U$5") (pin "5") (pinfunction "SI_5") (pintype "bidirectional"))
      (node (ref "U1") (pin "45") (pinfunction "IOB_44_SDO_45") (pintype "bidirectional"))
    )
    (net (code "69") (name "SS_PROG") (class "Default")
      (node (ref "R12") (pin "1") (pinfunction "1_1") (pintype "passive"))
      (node (ref "U1") (pin "49") (pinfunction "IOB_47_SS_49") (pintype "bidirectional"))
    )
    (net (code "70") (name "VPP_FAST") (class "Default")
      (node (ref "U1") (pin "76") (pinfunction "VPP_FAST_76") (pintype "power_in"))
    )
    (net (code "71") (name "VS") (class "Default")
      (node (ref "R3") (pin "2") (pinfunction "2_2") (pintype "passive"))
      (node (ref "U1") (pin "100") (pinfunction "IOT_95_100") (pintype "bidirectional"))
    )
    (net (code "72") (name "VYSNC") (class "Default")
      (node (ref "U$6") (pin "P$12") (pinfunction "P$12_P$12") (pintype "bidirectional"))
      (node (ref "U2") (pin "4") (pinfunction "A3_4") (pintype "bidirectional"))
    )
    (net (code "73") (name "unconnected-(3V3_REG-NC-Pad4)") (class "Default")
      (node (ref "3V3_REG") (pin "4") (pinfunction "NC_4") (pintype "no_connect"))
    )
    (net (code "74") (name "unconnected-(H1-MOUNT-PadB3,2)") (class "Default")
      (node (ref "H1") (pin "B3,2") (pinfunction "MOUNT_B3,2") (pintype "passive"))
    )
    (net (code "75") (name "unconnected-(H2-MOUNT-PadB3,2)") (class "Default")
      (node (ref "H2") (pin "B3,2") (pinfunction "MOUNT_B3,2") (pintype "passive"))
    )
    (net (code "76") (name "unconnected-(H3-MOUNT-PadB3,2)") (class "Default")
      (node (ref "H3") (pin "B3,2") (pinfunction "MOUNT_B3,2") (pintype "passive"))
    )
    (net (code "77") (name "unconnected-(H4-MOUNT-PadB3,2)") (class "Default")
      (node (ref "H4") (pin "B3,2") (pinfunction "MOUNT_B3,2") (pintype "passive"))
    )
    (net (code "78") (name "unconnected-(J1-Pad4)") (class "Default")
      (node (ref "J1") (pin "4") (pinfunction "4_4") (pintype "passive"))
    )
    (net (code "79") (name "unconnected-(J1-Pad9)") (class "Default")
      (node (ref "J1") (pin "9") (pinfunction "9_9") (pintype "passive"))
    )
    (net (code "80") (name "unconnected-(J1-Pad11)") (class "Default")
      (node (ref "J1") (pin "11") (pinfunction "11_11") (pintype "passive"))
    )
    (net (code "81") (name "unconnected-(J1-Pad12)") (class "Default")
      (node (ref "J1") (pin "12") (pinfunction "12_12") (pintype "passive"))
    )
    (net (code "82") (name "unconnected-(J1-Pad15)") (class "Default")
      (node (ref "J1") (pin "15") (pinfunction "15_15") (pintype "passive"))
    )
    (net (code "83") (name "unconnected-(J2-Pad6)") (class "Default")
      (node (ref "J2") (pin "6") (pinfunction "6_6") (pintype "passive"))
    )
    (net (code "84") (name "unconnected-(J2-Pad7)") (class "Default")
      (node (ref "J2") (pin "7") (pinfunction "7_7") (pintype "passive"))
    )
    (net (code "85") (name "unconnected-(SV1-Pad5)") (class "Default")
      (node (ref "SV1") (pin "5") (pinfunction "5_5") (pintype "passive"))
    )
    (net (code "86") (name "unconnected-(U$2-VBIAS-Pad4)") (class "Default")
      (node (ref "U$2") (pin "4") (pinfunction "VBIAS_4") (pintype "bidirectional"))
    )
    (net (code "87") (name "unconnected-(U$6-PadP$2)") (class "Default")
      (node (ref "U$6") (pin "P$2") (pinfunction "P$2_P$2") (pintype "bidirectional"))
    )
    (net (code "88") (name "unconnected-(U$6-PadP$3)") (class "Default")
      (node (ref "U$6") (pin "P$3") (pinfunction "P$3_P$3") (pintype "bidirectional"))
    )
    (net (code "89") (name "unconnected-(U$6-PadP$13)") (class "Default")
      (node (ref "U$6") (pin "P$13") (pinfunction "P$13_P$13") (pintype "bidirectional"))
    )
    (net (code "90") (name "unconnected-(U$6-PadP$17)") (class "Default")
      (node (ref "U$6") (pin "P$17") (pinfunction "P$17_P$17") (pintype "bidirectional"))
    )
    (net (code "91") (name "unconnected-(U$6-PadP$18)") (class "Default")
      (node (ref "U$6") (pin "P$18") (pinfunction "P$18_P$18") (pintype "bidirectional"))
    )
    (net (code "92") (name "unconnected-(U$6-PadP$19)") (class "Default")
      (node (ref "U$6") (pin "P$19") (pinfunction "P$19_P$19") (pintype "bidirectional"))
    )
    (net (code "93") (name "unconnected-(U$6-PadP$20)") (class "Default")
      (node (ref "U$6") (pin "P$20") (pinfunction "P$20_P$20") (pintype "bidirectional"))
    )
    (net (code "94") (name "unconnected-(U1-IOB_29-Pad29)") (class "Default")
      (node (ref "U1") (pin "29") (pinfunction "IOB_29_29") (pintype "bidirectional"))
    )
    (net (code "95") (name "unconnected-(U1-IOB_30-Pad30)") (class "Default")
      (node (ref "U1") (pin "30") (pinfunction "IOB_30_30") (pintype "bidirectional"))
    )
    (net (code "96") (name "unconnected-(U1-IOB_34-Pad36)") (class "Default")
      (node (ref "U1") (pin "36") (pinfunction "IOB_34_36") (pintype "bidirectional"))
    )
    (net (code "97") (name "unconnected-(U1-IOB_35_GBIN5-Pad33)") (class "Default")
      (node (ref "U1") (pin "33") (pinfunction "IOB_35_GBIN5_33") (pintype "bidirectional"))
    )
    (net (code "98") (name "unconnected-(U1-IOB_36_GBIN4-Pad34)") (class "Default")
      (node (ref "U1") (pin "34") (pinfunction "IOB_36_GBIN4_34") (pintype "bidirectional"))
    )
    (net (code "99") (name "unconnected-(U1-IOB_37-Pad37)") (class "Default")
      (node (ref "U1") (pin "37") (pinfunction "IOB_37_37") (pintype "bidirectional"))
    )
    (net (code "100") (name "unconnected-(U1-IOB_41-Pad40)") (class "Default")
      (node (ref "U1") (pin "40") (pinfunction "IOB_41_40") (pintype "bidirectional"))
    )
    (net (code "101") (name "unconnected-(U1-IOB_42_CBSEL0-Pad41)") (class "Default")
      (node (ref "U1") (pin "41") (pinfunction "IOB_42_CBSEL0_41") (pintype "bidirectional"))
    )
    (net (code "102") (name "unconnected-(U1-IOB_43_CBSEL1-Pad42)") (class "Default")
      (node (ref "U1") (pin "42") (pinfunction "IOB_43_CBSEL1_42") (pintype "bidirectional"))
    )
    (net (code "103") (name "unconnected-(U1-IOL_3B-Pad8)") (class "Default")
      (node (ref "U1") (pin "8") (pinfunction "IOL_3B_8") (pintype "bidirectional"))
    )
    (net (code "104") (name "unconnected-(U1-IOL_5A-Pad9)") (class "Default")
      (node (ref "U1") (pin "9") (pinfunction "IOL_5A_9") (pintype "bidirectional"))
    )
    (net (code "105") (name "unconnected-(U1-IOL_5B-Pad10)") (class "Default")
      (node (ref "U1") (pin "10") (pinfunction "IOL_5B_10") (pintype "bidirectional"))
    )
    (net (code "106") (name "unconnected-(U1-IOL_10A-Pad20)") (class "Default")
      (node (ref "U1") (pin "20") (pinfunction "IOL_10A_20") (pintype "bidirectional"))
    )
    (net (code "107") (name "unconnected-(U1-IOL_10B-Pad21)") (class "Default")
      (node (ref "U1") (pin "21") (pinfunction "IOL_10B_21") (pintype "bidirectional"))
    )
    (net (code "108") (name "unconnected-(U1-IOR_56-Pad56)") (class "Default")
      (node (ref "U1") (pin "56") (pinfunction "IOR_56_56") (pintype "bidirectional"))
    )
    (net (code "109") (name "unconnected-(U1-IOR_57-Pad57)") (class "Default")
      (node (ref "U1") (pin "57") (pinfunction "IOR_57_57") (pintype "bidirectional"))
    )
    (net (code "110") (name "unconnected-(U1-IOR_58-Pad59)") (class "Default")
      (node (ref "U1") (pin "59") (pinfunction "IOR_58_59") (pintype "bidirectional"))
    )
    (net (code "111") (name "unconnected-(U1-IOR_59-Pad60)") (class "Default")
      (node (ref "U1") (pin "60") (pinfunction "IOR_59_60") (pintype "bidirectional"))
    )
    (net (code "112") (name "unconnected-(U1-IOR_60_GBIN3-Pad62)") (class "Default")
      (node (ref "U1") (pin "62") (pinfunction "IOR_60_GBIN3_62") (pintype "bidirectional"))
    )
    (net (code "113") (name "unconnected-(U1-IOR_61_GBIN2-Pad63)") (class "Default")
      (node (ref "U1") (pin "63") (pinfunction "IOR_61_GBIN2_63") (pintype "bidirectional"))
    )
    (net (code "114") (name "unconnected-(U1-IOR_63-Pad64)") (class "Default")
      (node (ref "U1") (pin "64") (pinfunction "IOR_63_64") (pintype "bidirectional"))
    )
    (net (code "115") (name "unconnected-(U1-IOR_64-Pad65)") (class "Default")
      (node (ref "U1") (pin "65") (pinfunction "IOR_64_65") (pintype "bidirectional"))
    )
    (net (code "116") (name "unconnected-(U1-IOR_65-Pad66)") (class "Default")
      (node (ref "U1") (pin "66") (pinfunction "IOR_65_66") (pintype "bidirectional"))
    )
    (net (code "117") (name "unconnected-(U1-IOR_67-Pad68)") (class "Default")
      (node (ref "U1") (pin "68") (pinfunction "IOR_67_68") (pintype "bidirectional"))
    )
    (net (code "118") (name "unconnected-(U1-IOR_68-Pad69)") (class "Default")
      (node (ref "U1") (pin "69") (pinfunction "IOR_68_69") (pintype "bidirectional"))
    )
    (net (code "119") (name "unconnected-(U1-IOR_69-Pad71)") (class "Default")
      (node (ref "U1") (pin "71") (pinfunction "IOR_69_71") (pintype "bidirectional"))
    )
    (net (code "120") (name "unconnected-(U1-IOR_70-Pad72)") (class "Default")
      (node (ref "U1") (pin "72") (pinfunction "IOR_70_72") (pintype "bidirectional"))
    )
    (net (code "121") (name "unconnected-(U1-IOR_71-Pad73)") (class "Default")
      (node (ref "U1") (pin "73") (pinfunction "IOR_71_73") (pintype "bidirectional"))
    )
    (net (code "122") (name "unconnected-(U1-IOR_72-Pad74)") (class "Default")
      (node (ref "U1") (pin "74") (pinfunction "IOR_72_74") (pintype "bidirectional"))
    )
    (net (code "123") (name "unconnected-(U1-IOT_73-Pad78)") (class "Default")
      (node (ref "U1") (pin "78") (pinfunction "IOT_73_78") (pintype "bidirectional"))
    )
    (net (code "124") (name "unconnected-(U1-IOT_74-Pad79)") (class "Default")
      (node (ref "U1") (pin "79") (pinfunction "IOT_74_79") (pintype "bidirectional"))
    )
    (net (code "125") (name "unconnected-(U1-IOT_75-Pad80)") (class "Default")
      (node (ref "U1") (pin "80") (pinfunction "IOT_75_80") (pintype "bidirectional"))
    )
    (net (code "126") (name "unconnected-(U1-IOT_77-Pad81)") (class "Default")
      (node (ref "U1") (pin "81") (pinfunction "IOT_77_81") (pintype "bidirectional"))
    )
    (net (code "127") (name "unconnected-(U1-IOT_84_GBIN1-Pad89)") (class "Default")
      (node (ref "U1") (pin "89") (pinfunction "IOT_84_GBIN1_89") (pintype "bidirectional"))
    )
    (net (code "128") (name "unconnected-(U1-IOT_85_GBIN0-Pad90)") (class "Default")
      (node (ref "U1") (pin "90") (pinfunction "IOT_85_GBIN0_90") (pintype "bidirectional"))
    )
    (net (code "129") (name "unconnected-(U1-IOT_86-Pad91)") (class "Default")
      (node (ref "U1") (pin "91") (pinfunction "IOT_86_91") (pintype "bidirectional"))
    )
    (net (code "130") (name "unconnected-(U1-IOT_87-Pad93)") (class "Default")
      (node (ref "U1") (pin "93") (pinfunction "IOT_87_93") (pintype "bidirectional"))
    )
    (net (code "131") (name "unconnected-(U1-IOT_88-Pad94)") (class "Default")
      (node (ref "U1") (pin "94") (pinfunction "IOT_88_94") (pintype "bidirectional"))
    )
    (net (code "132") (name "unconnected-(U1-IOT_89-Pad95)") (class "Default")
      (node (ref "U1") (pin "95") (pinfunction "IOT_89_95") (pintype "bidirectional"))
    )
    (net (code "133") (name "unconnected-(U1-IOT_90-Pad96)") (class "Default")
      (node (ref "U1") (pin "96") (pinfunction "IOT_90_96") (pintype "bidirectional"))
    )
    (net (code "134") (name "unconnected-(U2-B5-Pad14)") (class "Default")
      (node (ref "U2") (pin "14") (pinfunction "B5_14") (pintype "bidirectional"))
    )
    (net (code "135") (name "unconnected-(U2-B6-Pad13)") (class "Default")
      (node (ref "U2") (pin "13") (pinfunction "B6_13") (pintype "bidirectional"))
    )
    (net (code "136") (name "unconnected-(U2-B7-Pad12)") (class "Default")
      (node (ref "U2") (pin "12") (pinfunction "B7_12") (pintype "bidirectional"))
    )
    (net (code "137") (name "unconnected-(U2-B8-Pad11)") (class "Default")
      (node (ref "U2") (pin "11") (pinfunction "B8_11") (pintype "bidirectional"))
    )
    (net (code "138") (name "unconnected-(U3-AREF-Pad42)") (class "Default")
      (node (ref "U3") (pin "42") (pinfunction "AREF_42") (pintype "bidirectional"))
    )
    (net (code "139") (name "unconnected-(U3-PB0(SS{slash}PCINT0)-Pad8)") (class "Default")
      (node (ref "U3") (pin "8") (pinfunction "PB0(SS/PCINT0)_8") (pintype "bidirectional"))
    )
    (net (code "140") (name "unconnected-(U3-PC7(ICP3{slash}CLK0{slash}OC4A)-Pad32)") (class "Default")
      (node (ref "U3") (pin "32") (pinfunction "PC7(ICP3/CLK0/OC4A)_32") (pintype "bidirectional"))
    )
    (net (code "141") (name "unconnected-(U3-PD2(RXD1{slash}INT2)-Pad20)") (class "Default")
      (node (ref "U3") (pin "20") (pinfunction "PD2(RXD1/INT2)_20") (pintype "bidirectional"))
    )
    (net (code "142") (name "unconnected-(U3-PD3(TXD1{slash}INT3)-Pad21)") (class "Default")
      (node (ref "U3") (pin "21") (pinfunction "PD3(TXD1/INT3)_21") (pintype "bidirectional"))
    )
    (net (code "143") (name "unconnected-(U3-PD5(XCLK1{slash}~{CTS})-Pad22)") (class "Default")
      (node (ref "U3") (pin "22") (pinfunction "PD5(XCLK1/~{CTS})_22") (pintype "bidirectional"))
    )
    (net (code "144") (name "unconnected-(U3-PD6(T1{slash}ADC9{slash}~{OC4D})-Pad26)") (class "Default")
      (node (ref "U3") (pin "26") (pinfunction "PD6(T1/ADC9/~{OC4D})_26") (pintype "bidirectional"))
    )
    (net (code "145") (name "unconnected-(U3-PE2(~{HWB})-Pad33)") (class "Default")
      (node (ref "U3") (pin "33") (pinfunction "PE2(~{HWB})_33") (pintype "bidirectional"))
    )
    (net (code "146") (name "unconnected-(U3-PF0(ADC0)-Pad41)") (class "Default")
      (node (ref "U3") (pin "41") (pinfunction "PF0(ADC0)_41") (pintype "bidirectional"))
    )
    (net (code "147") (name "unconnected-(U3-PF1(ADC1)-Pad40)") (class "Default")
      (node (ref "U3") (pin "40") (pinfunction "PF1(ADC1)_40") (pintype "bidirectional"))
    )
  )
)
